# PiModulos.net
KiCad netlist of a schematic drawn in Altium Designer
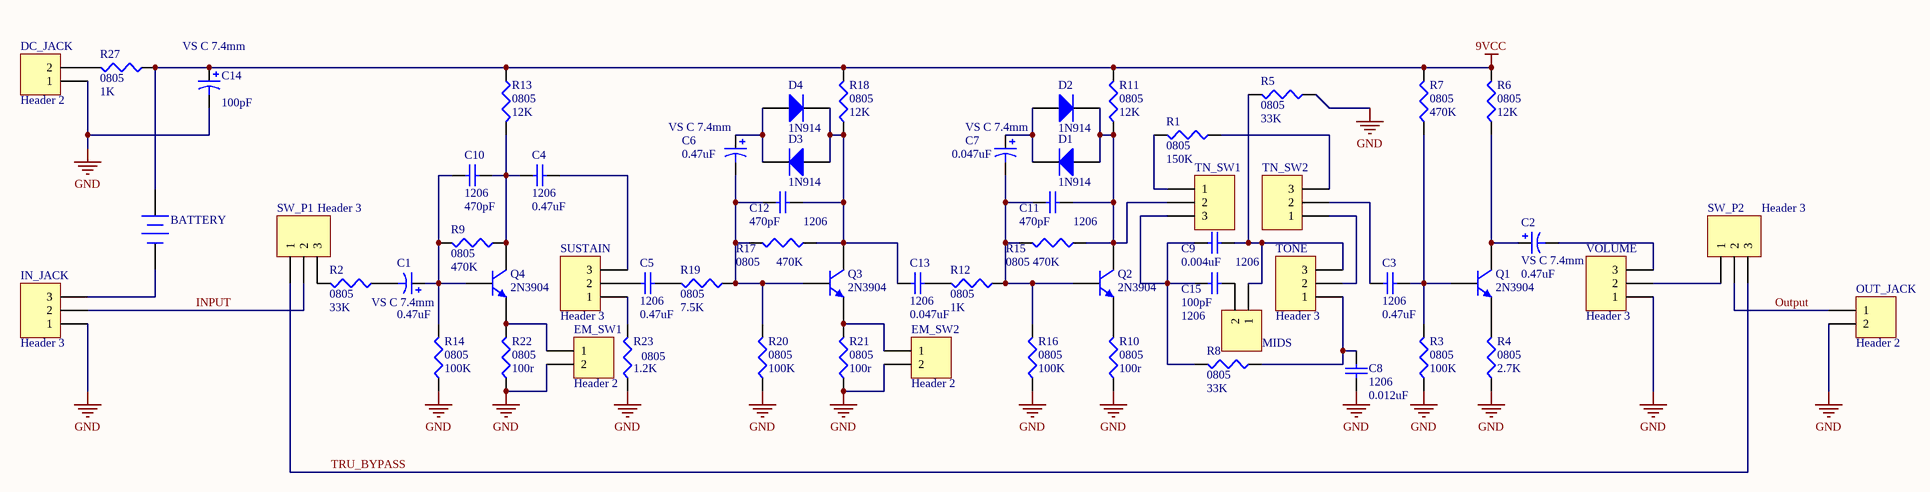
[diagram p0: PiModulos.SchDoc]

(export (version "E")
  (design (tool "Eeschema 10.0.6"))
  (components
    (comp (ref "BATTERY")
      (value "Battery")
      (footprint "BAT-2")
      (description "Multicell Battery")
      (fields (field (name "PUBLISHER") "Altium Limited"))
      (libsource (lib "Miscellaneous Devices") (part "Battery"))
    )
    (comp (ref "C1")
      (value "VS C 7.4mm")
      (footprint "Panasonic VS C")
      (description "Polarized Capacitor (Radial)")
      (fields (field (name "ALTIUM_VALUE") "0.47uF") (field (name "PUBLISHER") "Altium Limited"))
      (libsource (lib "Miscellaneous Devices") (part "Cap Pol1"))
    )
    (comp (ref "C2")
      (value "VS C 7.4mm")
      (footprint "Panasonic VS C")
      (description "Polarized Capacitor (Radial)")
      (fields (field (name "ALTIUM_VALUE") "0.47uF") (field (name "PUBLISHER") "Altium Limited"))
      (libsource (lib "Miscellaneous Devices") (part "Cap Pol1"))
    )
    (comp (ref "C3")
      (value "1206")
      (footprint "C1206")
      (description "Capacitor (Semiconductor SIM Model)")
      (fields (field (name "ALTIUM_VALUE") "0.47uF") (field (name "PUBLISHER") "Altium Limited"))
      (libsource (lib "Miscellaneous Devices") (part "Cap Semi"))
    )
    (comp (ref "C4")
      (value "1206")
      (footprint "C1206")
      (description "Capacitor (Semiconductor SIM Model)")
      (fields (field (name "ALTIUM_VALUE") "0.47uF") (field (name "PUBLISHER") "Altium Limited"))
      (libsource (lib "Miscellaneous Devices") (part "Cap Semi"))
    )
    (comp (ref "C5")
      (value "1206")
      (footprint "C1206")
      (description "Capacitor (Semiconductor SIM Model)")
      (fields (field (name "ALTIUM_VALUE") "0.47uF") (field (name "PUBLISHER") "Altium Limited"))
      (libsource (lib "Miscellaneous Devices") (part "Cap Semi"))
    )
    (comp (ref "C6")
      (value "VS C 7.4mm")
      (footprint "Panasonic VS C")
      (description "Polarized Capacitor (Radial)")
      (fields (field (name "ALTIUM_VALUE") "0.47uF") (field (name "PUBLISHER") "Altium Limited"))
      (libsource (lib "Miscellaneous Devices") (part "Cap Pol1"))
    )
    (comp (ref "C7")
      (value "VS C 7.4mm")
      (footprint "Panasonic VS C")
      (description "Polarized Capacitor (Radial)")
      (fields (field (name "ALTIUM_VALUE") "0.047uF") (field (name "PUBLISHER") "Altium Limited"))
      (libsource (lib "Miscellaneous Devices") (part "Cap Pol1"))
    )
    (comp (ref "C8")
      (value "1206")
      (footprint "C1206")
      (description "Capacitor (Semiconductor SIM Model)")
      (fields (field (name "ALTIUM_VALUE") "0.012uF") (field (name "PUBLISHER") "Altium Limited"))
      (libsource (lib "Miscellaneous Devices") (part "Cap Semi"))
    )
    (comp (ref "C9")
      (value "1206")
      (footprint "C1206")
      (description "Capacitor (Semiconductor SIM Model)")
      (fields (field (name "ALTIUM_VALUE") "0.004uF") (field (name "PUBLISHER") "Altium Limited"))
      (libsource (lib "Miscellaneous Devices") (part "Cap Semi"))
    )
    (comp (ref "C10")
      (value "1206")
      (footprint "C1206")
      (description "Capacitor (Semiconductor SIM Model)")
      (fields (field (name "ALTIUM_VALUE") "470pF") (field (name "PUBLISHER") "Altium Limited"))
      (libsource (lib "Miscellaneous Devices") (part "Cap Semi"))
    )
    (comp (ref "C11")
      (value "1206")
      (footprint "C1206")
      (description "Capacitor (Semiconductor SIM Model)")
      (fields (field (name "ALTIUM_VALUE") "470pF") (field (name "PUBLISHER") "Altium Limited"))
      (libsource (lib "Miscellaneous Devices") (part "Cap Semi"))
    )
    (comp (ref "C12")
      (value "1206")
      (footprint "C1206")
      (description "Capacitor (Semiconductor SIM Model)")
      (fields (field (name "ALTIUM_VALUE") "470pF") (field (name "PUBLISHER") "Altium Limited"))
      (libsource (lib "Miscellaneous Devices") (part "Cap Semi"))
    )
    (comp (ref "C13")
      (value "1206")
      (footprint "C1206")
      (description "Capacitor (Semiconductor SIM Model)")
      (fields (field (name "ALTIUM_VALUE") "0.047uF") (field (name "PUBLISHER") "Altium Limited"))
      (libsource (lib "Miscellaneous Devices") (part "Cap Semi"))
    )
    (comp (ref "C14")
      (value "VS C 7.4mm")
      (footprint "Panasonic VS C")
      (description "Polarized Capacitor (Radial)")
      (fields (field (name "ALTIUM_VALUE") "100pF") (field (name "PUBLISHER") "Altium Limited"))
      (libsource (lib "Miscellaneous Devices") (part "Cap Pol1"))
    )
    (comp (ref "C15")
      (value "1206")
      (footprint "C1206")
      (description "Capacitor (Semiconductor SIM Model)")
      (fields (field (name "ALTIUM_VALUE") "100pF") (field (name "PUBLISHER") "Altium Limited"))
      (libsource (lib "Miscellaneous Devices") (part "Cap Semi"))
    )
    (comp (ref "D1")
      (value "1N914")
      (footprint "DO-35")
      (description "High Conductance Fast Diode")
      (fields (field (name "PUBLISHER") "Altium Limited"))
      (libsource (lib "Miscellaneous Devices") (part "Diode 1N914"))
    )
    (comp (ref "D2")
      (value "1N914")
      (footprint "DO-35")
      (description "High Conductance Fast Diode")
      (fields (field (name "PUBLISHER") "Altium Limited"))
      (libsource (lib "Miscellaneous Devices") (part "Diode 1N914"))
    )
    (comp (ref "D3")
      (value "1N914")
      (footprint "DO-35")
      (description "High Conductance Fast Diode")
      (fields (field (name "PUBLISHER") "Altium Limited"))
      (libsource (lib "Miscellaneous Devices") (part "Diode 1N914"))
    )
    (comp (ref "D4")
      (value "1N914")
      (footprint "DO-35")
      (description "High Conductance Fast Diode")
      (fields (field (name "PUBLISHER") "Altium Limited"))
      (libsource (lib "Miscellaneous Devices") (part "Diode 1N914"))
    )
    (comp (ref "DC_JACK")
      (value "Header 2")
      (footprint "HDR1X2")
      (description "Header, 2-Pin")
      (fields (field (name "PUBLISHER") "Altium Limited"))
      (libsource (lib "") (part "Header 2_2"))
    )
    (comp (ref "EM_SW1")
      (value "Header 2")
      (footprint "HDR1X2")
      (description "Header, 2-Pin")
      (fields (field (name "PUBLISHER") "Altium Limited"))
      (libsource (lib "Miscellaneous Connectors") (part "Header 2"))
    )
    (comp (ref "EM_SW2")
      (value "Header 2")
      (footprint "HDR1X2")
      (description "Header, 2-Pin")
      (fields (field (name "PUBLISHER") "Altium Limited"))
      (libsource (lib "Miscellaneous Connectors") (part "Header 2"))
    )
    (comp (ref "IN_JACK")
      (value "Header 3")
      (footprint "HDR1X3")
      (description "Header, 3-Pin")
      (fields (field (name "PUBLISHER") "Altium Limited"))
      (libsource (lib "") (part "Header 3_2"))
    )
    (comp (ref "MIDS")
      (value "Header 2")
      (footprint "HDR1X2")
      (description "Header, 2-Pin")
      (fields (field (name "PUBLISHER") "Altium Limited"))
      (libsource (lib "") (part "Header 2_1"))
    )
    (comp (ref "OUT_JACK")
      (value "Header 2")
      (footprint "HDR1X2")
      (description "Header, 2-Pin")
      (fields (field (name "PUBLISHER") "Altium Limited"))
      (libsource (lib "Miscellaneous Connectors") (part "Header 2"))
    )
    (comp (ref "Q1")
      (value "2N3904")
      (footprint "TO-92A")
      (description "NPN General Purpose Amplifier")
      (fields (field (name "PUBLISHER") "Altium Limited"))
      (libsource (lib "Miscellaneous Devices") (part "2N3904"))
    )
    (comp (ref "Q2")
      (value "2N3904")
      (footprint "TO-92A")
      (description "NPN General Purpose Amplifier")
      (fields (field (name "PUBLISHER") "Altium Limited"))
      (libsource (lib "Miscellaneous Devices") (part "2N3904"))
    )
    (comp (ref "Q3")
      (value "2N3904")
      (footprint "TO-92A")
      (description "NPN General Purpose Amplifier")
      (fields (field (name "PUBLISHER") "Altium Limited"))
      (libsource (lib "Miscellaneous Devices") (part "2N3904"))
    )
    (comp (ref "Q4")
      (value "2N3904")
      (footprint "TO-92A")
      (description "NPN General Purpose Amplifier")
      (fields (field (name "PUBLISHER") "Altium Limited"))
      (libsource (lib "Miscellaneous Devices") (part "2N3904"))
    )
    (comp (ref "R1")
      (value "0805")
      (footprint "SM 0805 - gap trimmed")
      (description "Resistor")
      (fields (field (name "ALTIUM_VALUE") "150K") (field (name "PUBLISHER") "Altium Limited"))
      (libsource (lib "Miscellaneous Devices") (part "Res3"))
    )
    (comp (ref "R2")
      (value "0805")
      (footprint "SM 0805 - gap trimmed")
      (description "Resistor")
      (fields (field (name "ALTIUM_VALUE") "33K") (field (name "PUBLISHER") "Altium Limited"))
      (libsource (lib "Miscellaneous Devices") (part "Res3"))
    )
    (comp (ref "R3")
      (value "0805")
      (footprint "SM 0805 - gap trimmed")
      (description "Resistor")
      (fields (field (name "ALTIUM_VALUE") "100K") (field (name "PUBLISHER") "Altium Limited"))
      (libsource (lib "Miscellaneous Devices") (part "Res3"))
    )
    (comp (ref "R4")
      (value "0805")
      (footprint "SM 0805 - gap trimmed")
      (description "Resistor")
      (fields (field (name "ALTIUM_VALUE") "2.7K") (field (name "PUBLISHER") "Altium Limited"))
      (libsource (lib "Miscellaneous Devices") (part "Res3"))
    )
    (comp (ref "R5")
      (value "0805")
      (footprint "SM 0805 - gap trimmed")
      (description "Resistor")
      (fields (field (name "ALTIUM_VALUE") "33K") (field (name "PUBLISHER") "Altium Limited"))
      (libsource (lib "Miscellaneous Devices") (part "Res3"))
    )
    (comp (ref "R6")
      (value "0805")
      (footprint "SM 0805 - gap trimmed")
      (description "Resistor")
      (fields (field (name "ALTIUM_VALUE") "12K") (field (name "PUBLISHER") "Altium Limited"))
      (libsource (lib "Miscellaneous Devices") (part "Res3"))
    )
    (comp (ref "R7")
      (value "0805")
      (footprint "SM 0805 - gap trimmed")
      (description "Resistor")
      (fields (field (name "ALTIUM_VALUE") "470K") (field (name "PUBLISHER") "Altium Limited"))
      (libsource (lib "Miscellaneous Devices") (part "Res3"))
    )
    (comp (ref "R8")
      (value "0805")
      (footprint "SM 0805 - gap trimmed")
      (description "Resistor")
      (fields (field (name "ALTIUM_VALUE") "33K") (field (name "PUBLISHER") "Altium Limited"))
      (libsource (lib "Miscellaneous Devices") (part "Res3"))
    )
    (comp (ref "R9")
      (value "0805")
      (footprint "SM 0805 - gap trimmed")
      (description "Resistor")
      (fields (field (name "ALTIUM_VALUE") "470K") (field (name "PUBLISHER") "Altium Limited"))
      (libsource (lib "Miscellaneous Devices") (part "Res3"))
    )
    (comp (ref "R10")
      (value "0805")
      (footprint "SM 0805 - gap trimmed")
      (description "Resistor")
      (fields (field (name "ALTIUM_VALUE") "100r") (field (name "PUBLISHER") "Altium Limited"))
      (libsource (lib "Miscellaneous Devices") (part "Res3"))
    )
    (comp (ref "R11")
      (value "0805")
      (footprint "SM 0805 - gap trimmed")
      (description "Resistor")
      (fields (field (name "ALTIUM_VALUE") "12K") (field (name "PUBLISHER") "Altium Limited"))
      (libsource (lib "Miscellaneous Devices") (part "Res3"))
    )
    (comp (ref "R12")
      (value "0805")
      (footprint "SM 0805 - gap trimmed")
      (description "Resistor")
      (fields (field (name "ALTIUM_VALUE") "1K") (field (name "PUBLISHER") "Altium Limited"))
      (libsource (lib "Miscellaneous Devices") (part "Res3"))
    )
    (comp (ref "R13")
      (value "0805")
      (footprint "SM 0805 - gap trimmed")
      (description "Resistor")
      (fields (field (name "ALTIUM_VALUE") "12K") (field (name "PUBLISHER") "Altium Limited"))
      (libsource (lib "Miscellaneous Devices") (part "Res3"))
    )
    (comp (ref "R14")
      (value "0805")
      (footprint "SM 0805 - gap trimmed")
      (description "Resistor")
      (fields (field (name "ALTIUM_VALUE") "100K") (field (name "PUBLISHER") "Altium Limited"))
      (libsource (lib "Miscellaneous Devices") (part "Res3"))
    )
    (comp (ref "R15")
      (value "0805")
      (footprint "SM 0805 - gap trimmed")
      (description "Resistor")
      (fields (field (name "ALTIUM_VALUE") "470K") (field (name "PUBLISHER") "Altium Limited"))
      (libsource (lib "Miscellaneous Devices") (part "Res3"))
    )
    (comp (ref "R16")
      (value "0805")
      (footprint "SM 0805 - gap trimmed")
      (description "Resistor")
      (fields (field (name "ALTIUM_VALUE") "100K") (field (name "PUBLISHER") "Altium Limited"))
      (libsource (lib "Miscellaneous Devices") (part "Res3"))
    )
    (comp (ref "R17")
      (value "0805")
      (footprint "SM 0805 - gap trimmed")
      (description "Resistor")
      (fields (field (name "ALTIUM_VALUE") "470K") (field (name "PUBLISHER") "Altium Limited"))
      (libsource (lib "Miscellaneous Devices") (part "Res3"))
    )
    (comp (ref "R18")
      (value "0805")
      (footprint "SM 0805 - gap trimmed")
      (description "Resistor")
      (fields (field (name "ALTIUM_VALUE") "12K") (field (name "PUBLISHER") "Altium Limited"))
      (libsource (lib "Miscellaneous Devices") (part "Res3"))
    )
    (comp (ref "R19")
      (value "0805")
      (footprint "SM 0805 - gap trimmed")
      (description "Resistor")
      (fields (field (name "ALTIUM_VALUE") "7.5K") (field (name "PUBLISHER") "Altium Limited"))
      (libsource (lib "Miscellaneous Devices") (part "Res3"))
    )
    (comp (ref "R20")
      (value "0805")
      (footprint "SM 0805 - gap trimmed")
      (description "Resistor")
      (fields (field (name "ALTIUM_VALUE") "100K") (field (name "PUBLISHER") "Altium Limited"))
      (libsource (lib "Miscellaneous Devices") (part "Res3"))
    )
    (comp (ref "R21")
      (value "0805")
      (footprint "SM 0805 - gap trimmed")
      (description "Resistor")
      (fields (field (name "ALTIUM_VALUE") "100r") (field (name "PUBLISHER") "Altium Limited"))
      (libsource (lib "Miscellaneous Devices") (part "Res3"))
    )
    (comp (ref "R22")
      (value "0805")
      (footprint "SM 0805 - gap trimmed")
      (description "Resistor")
      (fields (field (name "ALTIUM_VALUE") "100r") (field (name "PUBLISHER") "Altium Limited"))
      (libsource (lib "Miscellaneous Devices") (part "Res3"))
    )
    (comp (ref "R23")
      (value "0805")
      (footprint "SM 0805 - gap trimmed")
      (description "Resistor")
      (fields (field (name "ALTIUM_VALUE") "1.2K") (field (name "PUBLISHER") "Altium Limited"))
      (libsource (lib "Miscellaneous Devices") (part "Res3"))
    )
    (comp (ref "R27")
      (value "0805")
      (footprint "SM 0805 - gap trimmed")
      (description "Resistor")
      (fields (field (name "ALTIUM_VALUE") "1K") (field (name "PUBLISHER") "Altium Limited"))
      (libsource (lib "Miscellaneous Devices") (part "Res3"))
    )
    (comp (ref "SUSTAIN")
      (value "Header 3")
      (footprint "HDR1X3")
      (description "Header, 3-Pin")
      (fields (field (name "PUBLISHER") "Altium Limited"))
      (libsource (lib "") (part "Header 3_2"))
    )
    (comp (ref "SW_P1")
      (value "Header 3")
      (footprint "HDR1X3")
      (description "Header, 3-Pin")
      (fields (field (name "PUBLISHER") "Altium Limited"))
      (libsource (lib "Miscellaneous Connectors") (part "Header 3"))
    )
    (comp (ref "SW_P2")
      (value "Header 3")
      (footprint "HDR1X3")
      (description "Header, 3-Pin")
      (fields (field (name "PUBLISHER") "Altium Limited"))
      (libsource (lib "Miscellaneous Connectors") (part "Header 3"))
    )
    (comp (ref "TN_SW1")
      (value "Header 3")
      (footprint "HDR1X3")
      (description "Header, 3-Pin")
      (fields (field (name "PUBLISHER") "Altium Limited"))
      (libsource (lib "") (part "Header 3_1"))
    )
    (comp (ref "TN_SW2")
      (value "Header 3")
      (footprint "HDR1X3")
      (description "Header, 3-Pin")
      (fields (field (name "PUBLISHER") "Altium Limited"))
      (libsource (lib "") (part "Header 3_2"))
    )
    (comp (ref "TONE")
      (value "Header 3")
      (footprint "HDR1X3")
      (description "Header, 3-Pin")
      (fields (field (name "PUBLISHER") "Altium Limited"))
      (libsource (lib "") (part "Header 3_2"))
    )
    (comp (ref "VOLUME")
      (value "Header 3")
      (footprint "HDR1X3")
      (description "Header, 3-Pin")
      (fields (field (name "PUBLISHER") "Altium Limited"))
      (libsource (lib "") (part "Header 3_2"))
    )
  )
  (nets
    (net (code "1") (name "/INPUT") (class "Default")
      (node (ref "IN_JACK") (pin "2") (pinfunction "2_2") (pintype "passive"))
      (node (ref "SW_P1") (pin "2") (pinfunction "2_2") (pintype "passive"))
    )
    (net (code "2") (name "/Output") (class "Default")
      (node (ref "OUT_JACK") (pin "1") (pinfunction "1_1") (pintype "passive"))
      (node (ref "SW_P2") (pin "2") (pinfunction "2_2") (pintype "passive"))
    )
    (net (code "3") (name "/TRU_BYPASS") (class "Default")
      (node (ref "SW_P1") (pin "1") (pinfunction "1_1") (pintype "passive"))
      (node (ref "SW_P2") (pin "3") (pinfunction "3_3") (pintype "passive"))
    )
    (net (code "4") (name "9VCC") (class "Default")
      (node (ref "BATTERY") (pin "1") (pinfunction "+_1") (pintype "passive"))
      (node (ref "C14") (pin "1") (pinfunction "1_1") (pintype "passive"))
      (node (ref "R11") (pin "2") (pinfunction "2_2") (pintype "passive"))
      (node (ref "R13") (pin "1") (pinfunction "1_1") (pintype "passive"))
      (node (ref "R18") (pin "2") (pinfunction "2_2") (pintype "passive"))
      (node (ref "R27") (pin "1") (pinfunction "1_1") (pintype "passive"))
      (node (ref "R6") (pin "2") (pinfunction "2_2") (pintype "passive"))
      (node (ref "R7") (pin "2") (pinfunction "2_2") (pintype "passive"))
    )
    (net (code "5") (name "GND") (class "Default")
      (node (ref "C14") (pin "2") (pinfunction "2_2") (pintype "passive"))
      (node (ref "C8") (pin "1") (pinfunction "1_1") (pintype "passive"))
      (node (ref "DC_JACK") (pin "1") (pinfunction "1_1") (pintype "passive"))
      (node (ref "EM_SW1") (pin "2") (pinfunction "2_2") (pintype "passive"))
      (node (ref "EM_SW2") (pin "2") (pinfunction "2_2") (pintype "passive"))
      (node (ref "IN_JACK") (pin "1") (pinfunction "1_1") (pintype "passive"))
      (node (ref "OUT_JACK") (pin "2") (pinfunction "2_2") (pintype "passive"))
      (node (ref "R10") (pin "1") (pinfunction "1_1") (pintype "passive"))
      (node (ref "R14") (pin "1") (pinfunction "1_1") (pintype "passive"))
      (node (ref "R16") (pin "1") (pinfunction "1_1") (pintype "passive"))
      (node (ref "R20") (pin "1") (pinfunction "1_1") (pintype "passive"))
      (node (ref "R21") (pin "1") (pinfunction "1_1") (pintype "passive"))
      (node (ref "R22") (pin "1") (pinfunction "1_1") (pintype "passive"))
      (node (ref "R23") (pin "1") (pinfunction "1_1") (pintype "passive"))
      (node (ref "R3") (pin "1") (pinfunction "1_1") (pintype "passive"))
      (node (ref "R4") (pin "1") (pinfunction "1_1") (pintype "passive"))
      (node (ref "R5") (pin "1") (pinfunction "1_1") (pintype "passive"))
      (node (ref "VOLUME") (pin "1") (pinfunction "1_1") (pintype "passive"))
    )
    (net (code "6") (name "Net-(BATTERY--)") (class "Default")
      (node (ref "BATTERY") (pin "2") (pinfunction "-_2") (pintype "passive"))
      (node (ref "IN_JACK") (pin "3") (pinfunction "3_3") (pintype "passive"))
    )
    (net (code "7") (name "Net-(C1-Pad2)") (class "Default")
      (node (ref "C1") (pin "2") (pinfunction "2_2") (pintype "passive"))
      (node (ref "R2") (pin "1") (pinfunction "1_1") (pintype "passive"))
    )
    (net (code "8") (name "Net-(C2-Pad2)") (class "Default")
      (node (ref "C2") (pin "2") (pinfunction "2_2") (pintype "passive"))
      (node (ref "VOLUME") (pin "3") (pinfunction "3_3") (pintype "passive"))
    )
    (net (code "9") (name "Net-(C3-Pad1)") (class "Default")
      (node (ref "C3") (pin "1") (pinfunction "1_1") (pintype "passive"))
      (node (ref "TN_SW2") (pin "2") (pinfunction "2_2") (pintype "passive"))
    )
    (net (code "10") (name "Net-(C4-Pad2)") (class "Default")
      (node (ref "C4") (pin "2") (pinfunction "2_2") (pintype "passive"))
      (node (ref "SUSTAIN") (pin "3") (pinfunction "3_3") (pintype "passive"))
    )
    (net (code "11") (name "Net-(C5-Pad1)") (class "Default")
      (node (ref "C5") (pin "1") (pinfunction "1_1") (pintype "passive"))
      (node (ref "SUSTAIN") (pin "2") (pinfunction "2_2") (pintype "passive"))
    )
    (net (code "12") (name "Net-(C5-Pad2)") (class "Default")
      (node (ref "C5") (pin "2") (pinfunction "2_2") (pintype "passive"))
      (node (ref "R19") (pin "2") (pinfunction "2_2") (pintype "passive"))
    )
    (net (code "13") (name "Net-(C8-Pad2)") (class "Default")
      (node (ref "C8") (pin "2") (pinfunction "2_2") (pintype "passive"))
      (node (ref "R8") (pin "1") (pinfunction "1_1") (pintype "passive"))
      (node (ref "TONE") (pin "1") (pinfunction "1_1") (pintype "passive"))
    )
    (net (code "14") (name "Net-(C9-Pad2)") (class "Default")
      (node (ref "C9") (pin "2") (pinfunction "2_2") (pintype "passive"))
      (node (ref "MIDS") (pin "1") (pinfunction "1_1") (pintype "passive"))
      (node (ref "R5") (pin "2") (pinfunction "2_2") (pintype "passive"))
      (node (ref "TONE") (pin "3") (pinfunction "3_3") (pintype "passive"))
    )
    (net (code "15") (name "Net-(C13-Pad2)") (class "Default")
      (node (ref "C13") (pin "2") (pinfunction "2_2") (pintype "passive"))
      (node (ref "R12") (pin "2") (pinfunction "2_2") (pintype "passive"))
    )
    (net (code "16") (name "Net-(C15-Pad1)") (class "Default")
      (node (ref "C15") (pin "1") (pinfunction "1_1") (pintype "passive"))
      (node (ref "C9") (pin "1") (pinfunction "1_1") (pintype "passive"))
      (node (ref "R8") (pin "2") (pinfunction "2_2") (pintype "passive"))
      (node (ref "TN_SW1") (pin "3") (pinfunction "3_3") (pintype "passive"))
    )
    (net (code "17") (name "Net-(C15-Pad2)") (class "Default")
      (node (ref "C15") (pin "2") (pinfunction "2_2") (pintype "passive"))
      (node (ref "MIDS") (pin "2") (pinfunction "2_2") (pintype "passive"))
    )
    (net (code "18") (name "Net-(D1-A)") (class "Default")
      (node (ref "C11") (pin "2") (pinfunction "2_2") (pintype "passive"))
      (node (ref "D1") (pin "1") (pinfunction "A_1") (pintype "passive"))
      (node (ref "D2") (pin "2") (pinfunction "K_2") (pintype "passive"))
      (node (ref "Q2") (pin "3") (pinfunction "C_3") (pintype "passive"))
      (node (ref "R11") (pin "1") (pinfunction "1_1") (pintype "passive"))
      (node (ref "R15") (pin "1") (pinfunction "1_1") (pintype "passive"))
      (node (ref "TN_SW1") (pin "2") (pinfunction "2_2") (pintype "passive"))
    )
    (net (code "19") (name "Net-(D1-K)") (class "Default")
      (node (ref "C7") (pin "1") (pinfunction "1_1") (pintype "passive"))
      (node (ref "D1") (pin "2") (pinfunction "K_2") (pintype "passive"))
      (node (ref "D2") (pin "1") (pinfunction "A_1") (pintype "passive"))
    )
    (net (code "20") (name "Net-(D3-A)") (class "Default")
      (node (ref "C12") (pin "2") (pinfunction "2_2") (pintype "passive"))
      (node (ref "C13") (pin "1") (pinfunction "1_1") (pintype "passive"))
      (node (ref "D3") (pin "1") (pinfunction "A_1") (pintype "passive"))
      (node (ref "D4") (pin "2") (pinfunction "K_2") (pintype "passive"))
      (node (ref "Q3") (pin "3") (pinfunction "C_3") (pintype "passive"))
      (node (ref "R17") (pin "1") (pinfunction "1_1") (pintype "passive"))
      (node (ref "R18") (pin "1") (pinfunction "1_1") (pintype "passive"))
    )
    (net (code "21") (name "Net-(D3-K)") (class "Default")
      (node (ref "C6") (pin "1") (pinfunction "1_1") (pintype "passive"))
      (node (ref "D3") (pin "2") (pinfunction "K_2") (pintype "passive"))
      (node (ref "D4") (pin "1") (pinfunction "A_1") (pintype "passive"))
    )
    (net (code "22") (name "Net-(DC_JACK-Pad2)") (class "Default")
      (node (ref "DC_JACK") (pin "2") (pinfunction "2_2") (pintype "passive"))
      (node (ref "R27") (pin "2") (pinfunction "2_2") (pintype "passive"))
    )
    (net (code "23") (name "Net-(Q1-B)") (class "Default")
      (node (ref "C3") (pin "2") (pinfunction "2_2") (pintype "passive"))
      (node (ref "Q1") (pin "2") (pinfunction "B_2") (pintype "passive"))
      (node (ref "R3") (pin "2") (pinfunction "2_2") (pintype "passive"))
      (node (ref "R7") (pin "1") (pinfunction "1_1") (pintype "passive"))
    )
    (net (code "24") (name "Net-(Q1-C)") (class "Default")
      (node (ref "C2") (pin "1") (pinfunction "1_1") (pintype "passive"))
      (node (ref "Q1") (pin "3") (pinfunction "C_3") (pintype "passive"))
      (node (ref "R6") (pin "1") (pinfunction "1_1") (pintype "passive"))
    )
    (net (code "25") (name "Net-(Q1-E)") (class "Default")
      (node (ref "Q1") (pin "1") (pinfunction "E_1") (pintype "passive"))
      (node (ref "R4") (pin "2") (pinfunction "2_2") (pintype "passive"))
    )
    (net (code "26") (name "Net-(Q2-B)") (class "Default")
      (node (ref "C11") (pin "1") (pinfunction "1_1") (pintype "passive"))
      (node (ref "C7") (pin "2") (pinfunction "2_2") (pintype "passive"))
      (node (ref "Q2") (pin "2") (pinfunction "B_2") (pintype "passive"))
      (node (ref "R12") (pin "1") (pinfunction "1_1") (pintype "passive"))
      (node (ref "R15") (pin "2") (pinfunction "2_2") (pintype "passive"))
      (node (ref "R16") (pin "2") (pinfunction "2_2") (pintype "passive"))
    )
    (net (code "27") (name "Net-(Q2-E)") (class "Default")
      (node (ref "Q2") (pin "1") (pinfunction "E_1") (pintype "passive"))
      (node (ref "R10") (pin "2") (pinfunction "2_2") (pintype "passive"))
    )
    (net (code "28") (name "Net-(Q3-B)") (class "Default")
      (node (ref "C12") (pin "1") (pinfunction "1_1") (pintype "passive"))
      (node (ref "C6") (pin "2") (pinfunction "2_2") (pintype "passive"))
      (node (ref "Q3") (pin "2") (pinfunction "B_2") (pintype "passive"))
      (node (ref "R17") (pin "2") (pinfunction "2_2") (pintype "passive"))
      (node (ref "R19") (pin "1") (pinfunction "1_1") (pintype "passive"))
      (node (ref "R20") (pin "2") (pinfunction "2_2") (pintype "passive"))
    )
    (net (code "29") (name "Net-(Q3-E)") (class "Default")
      (node (ref "EM_SW2") (pin "1") (pinfunction "1_1") (pintype "passive"))
      (node (ref "Q3") (pin "1") (pinfunction "E_1") (pintype "passive"))
      (node (ref "R21") (pin "2") (pinfunction "2_2") (pintype "passive"))
    )
    (net (code "30") (name "Net-(Q4-B)") (class "Default")
      (node (ref "C1") (pin "1") (pinfunction "1_1") (pintype "passive"))
      (node (ref "C10") (pin "1") (pinfunction "1_1") (pintype "passive"))
      (node (ref "Q4") (pin "2") (pinfunction "B_2") (pintype "passive"))
      (node (ref "R14") (pin "2") (pinfunction "2_2") (pintype "passive"))
      (node (ref "R9") (pin "2") (pinfunction "2_2") (pintype "passive"))
    )
    (net (code "31") (name "Net-(Q4-C)") (class "Default")
      (node (ref "C10") (pin "2") (pinfunction "2_2") (pintype "passive"))
      (node (ref "C4") (pin "1") (pinfunction "1_1") (pintype "passive"))
      (node (ref "Q4") (pin "3") (pinfunction "C_3") (pintype "passive"))
      (node (ref "R13") (pin "2") (pinfunction "2_2") (pintype "passive"))
      (node (ref "R9") (pin "1") (pinfunction "1_1") (pintype "passive"))
    )
    (net (code "32") (name "Net-(Q4-E)") (class "Default")
      (node (ref "EM_SW1") (pin "1") (pinfunction "1_1") (pintype "passive"))
      (node (ref "Q4") (pin "1") (pinfunction "E_1") (pintype "passive"))
      (node (ref "R22") (pin "2") (pinfunction "2_2") (pintype "passive"))
    )
    (net (code "33") (name "Net-(R1-Pad1)") (class "Default")
      (node (ref "R1") (pin "1") (pinfunction "1_1") (pintype "passive"))
      (node (ref "TN_SW2") (pin "3") (pinfunction "3_3") (pintype "passive"))
    )
    (net (code "34") (name "Net-(R1-Pad2)") (class "Default")
      (node (ref "R1") (pin "2") (pinfunction "2_2") (pintype "passive"))
      (node (ref "TN_SW1") (pin "1") (pinfunction "1_1") (pintype "passive"))
    )
    (net (code "35") (name "Net-(R2-Pad2)") (class "Default")
      (node (ref "R2") (pin "2") (pinfunction "2_2") (pintype "passive"))
      (node (ref "SW_P1") (pin "3") (pinfunction "3_3") (pintype "passive"))
    )
    (net (code "36") (name "Net-(R23-Pad2)") (class "Default")
      (node (ref "R23") (pin "2") (pinfunction "2_2") (pintype "passive"))
      (node (ref "SUSTAIN") (pin "1") (pinfunction "1_1") (pintype "passive"))
    )
    (net (code "37") (name "Net-(SW_P2-Pad1)") (class "Default")
      (node (ref "SW_P2") (pin "1") (pinfunction "1_1") (pintype "passive"))
      (node (ref "VOLUME") (pin "2") (pinfunction "2_2") (pintype "passive"))
    )
    (net (code "38") (name "Net-(TN_SW2-Pad1)") (class "Default")
      (node (ref "TN_SW2") (pin "1") (pinfunction "1_1") (pintype "passive"))
      (node (ref "TONE") (pin "2") (pinfunction "2_2") (pintype "passive"))
    )
  )
)
